# Uni_Seriell.net
KiCad netlist of a schematic drawn in EAGLE
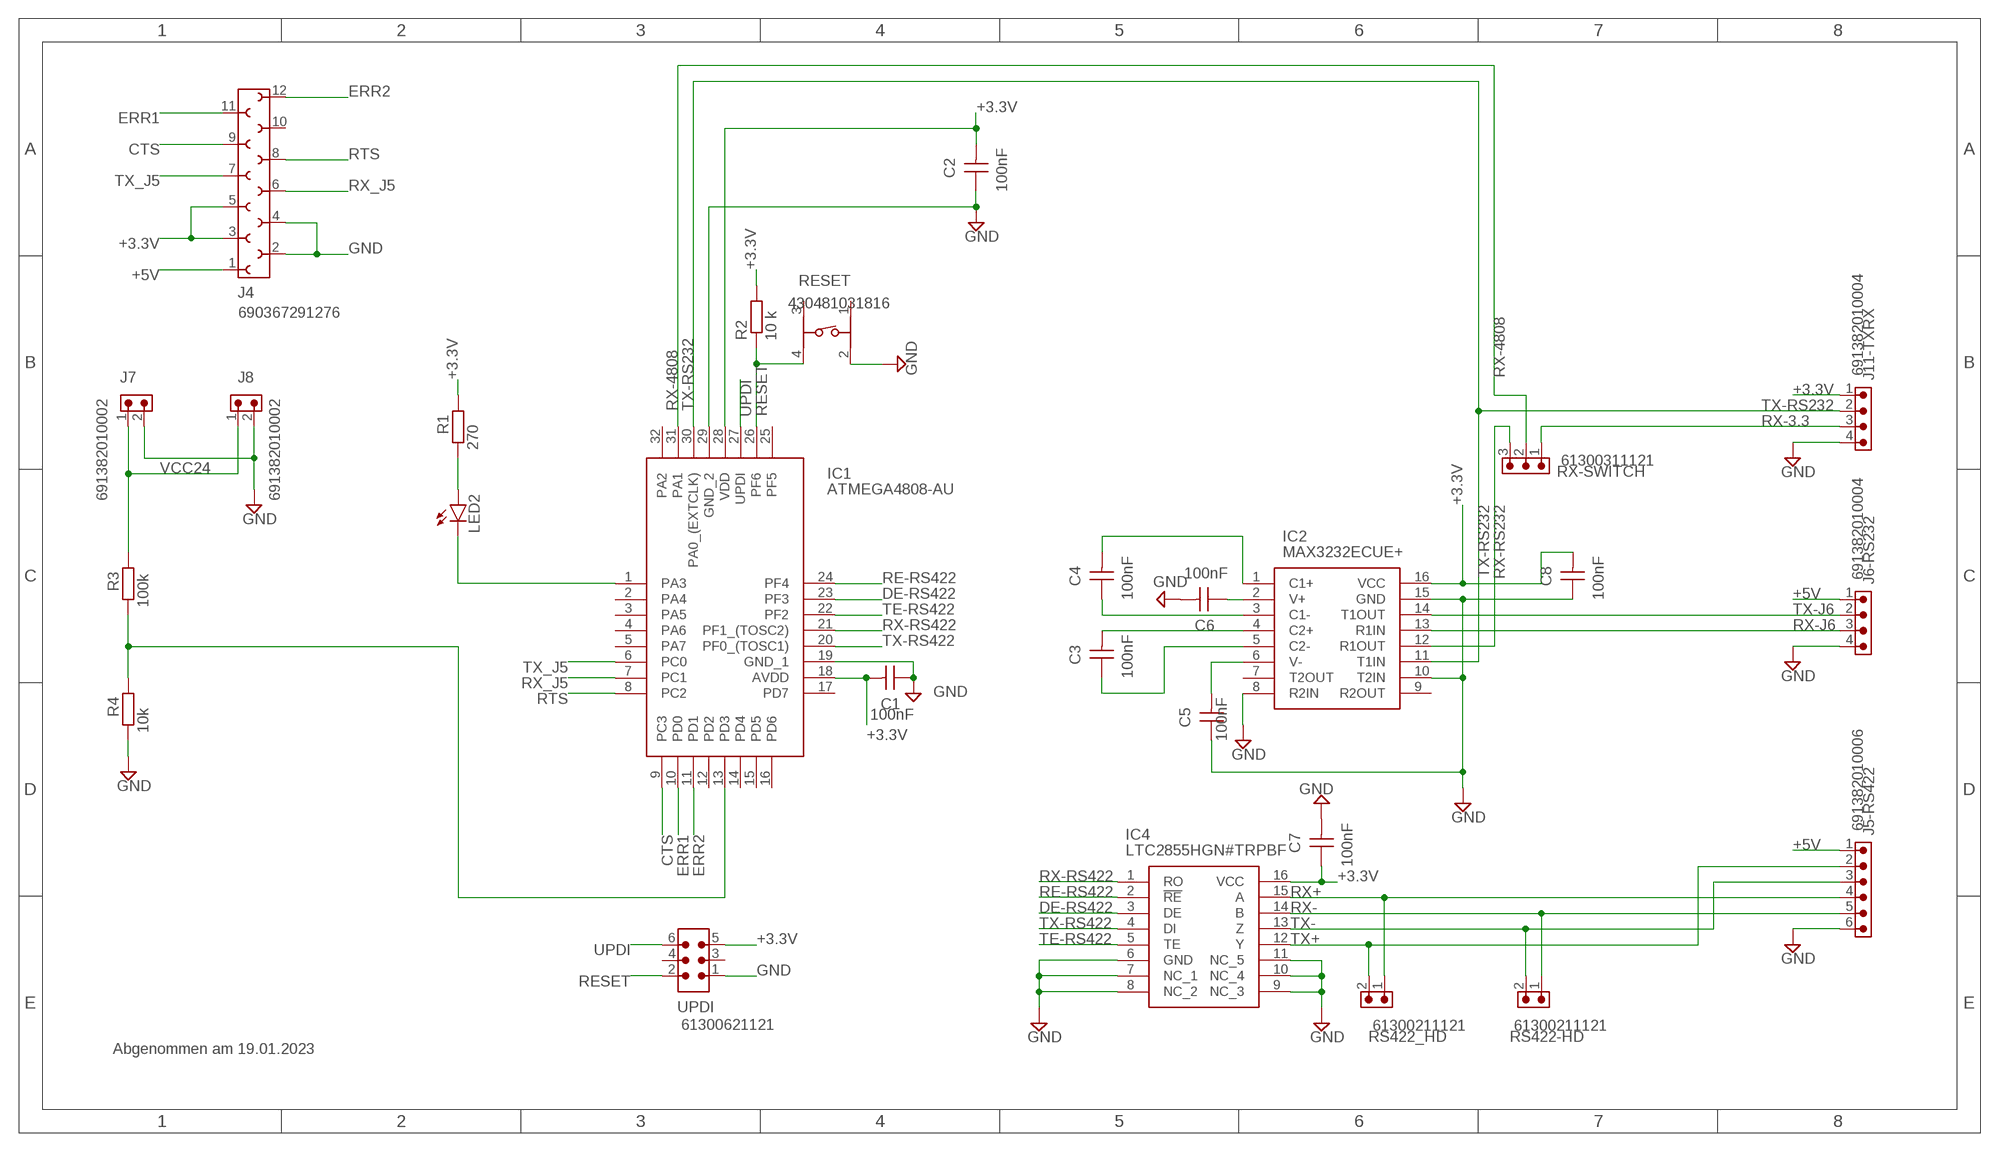
[diagram p0: schematic, sheet 1]

(export (version "E")
  (design (tool "Eeschema 10.0.6"))
  (components
    (comp (ref "C1")
      (value "100nF")
      (footprint "eagle-import:WCAP-CSST_0805")
      (libsource (lib "eagle-import") (part "WCAP-CSST_0805_885382207007"))
    )
    (comp (ref "C2")
      (value "100nF")
      (footprint "eagle-import:WCAP-CSST_0805")
      (libsource (lib "eagle-import") (part "WCAP-CSST_0805_885382207007"))
    )
    (comp (ref "C3")
      (value "100nF")
      (footprint "eagle-import:WCAP-CSST_0805")
      (libsource (lib "eagle-import") (part "WCAP-CSST_0805_885382207007"))
    )
    (comp (ref "C4")
      (value "100nF")
      (footprint "eagle-import:WCAP-CSST_0805")
      (libsource (lib "eagle-import") (part "WCAP-CSST_0805_885382207007"))
    )
    (comp (ref "C5")
      (value "100nF")
      (footprint "eagle-import:WCAP-CSST_0805")
      (libsource (lib "eagle-import") (part "WCAP-CSST_0805_885382207007"))
    )
    (comp (ref "C6")
      (value "100nF")
      (footprint "eagle-import:WCAP-CSST_0805")
      (libsource (lib "eagle-import") (part "WCAP-CSST_0805_885382207007"))
    )
    (comp (ref "C7")
      (value "100nF")
      (footprint "eagle-import:WCAP-CSST_0805")
      (libsource (lib "eagle-import") (part "WCAP-CSST_0805_885382207007"))
    )
    (comp (ref "C8")
      (value "100nF")
      (footprint "eagle-import:WCAP-CSST_0805")
      (libsource (lib "eagle-import") (part "WCAP-CSST_0805_885382207007"))
    )
    (comp (ref "IC1")
      (value "ATMEGA4808-AU")
      (footprint "eagle-import:QFP80P900X900X120-32N")
      (fields (field (name "MOUSER_PART_NUMBER") "556-ATMEGA4808-AU"))
      (libsource (lib "eagle-import") (part "ATMEGA4808-AU"))
    )
    (comp (ref "IC2")
      (value "MAX3232ECUE+")
      (footprint "eagle-import:SOP65P640X110-16N")
      (fields (field (name "MOUSER_PART_NUMBER") "700-MAX3232ECUE"))
      (libsource (lib "eagle-import") (part "MAX3232ECUE+"))
    )
    (comp (ref "IC4")
      (value "LTC2855HGN#TRPBF")
      (footprint "eagle-import:SOP64P601X175-16N")
      (fields (field (name "MOUSER_PART_NUMBER") "584-LTC2855HGN#TRPBF"))
      (libsource (lib "eagle-import") (part "LTC2855HGN#TRPBF"))
    )
    (comp (ref "J4")
      (value "690367291276")
      (footprint "eagle-import:690367291276")
      (libsource (lib "eagle-import") (part "690367291276"))
    )
    (comp (ref "J5-RS422")
      (value "691382010006")
      (footprint "eagle-import:691382010006")
      (libsource (lib "eagle-import") (part "691382010006"))
    )
    (comp (ref "J6-RS232")
      (value "691382010004")
      (footprint "eagle-import:691382010004")
      (libsource (lib "eagle-import") (part "691382010004"))
    )
    (comp (ref "J7")
      (value "691382010002")
      (footprint "eagle-import:691382010002")
      (libsource (lib "eagle-import") (part "691382010002"))
    )
    (comp (ref "J8")
      (value "691382010002")
      (footprint "eagle-import:691382010002")
      (libsource (lib "eagle-import") (part "691382010002"))
    )
    (comp (ref "J11-TXRX")
      (value "691382010004")
      (footprint "eagle-import:691382010004")
      (libsource (lib "eagle-import") (part "691382010004"))
    )
    (comp (ref "LED2")
      (value "LEDCHIP-LED0805")
      (footprint "eagle-import:CHIP-LED0805")
      (libsource (lib "eagle-import") (part "LEDCHIP-LED0805"))
    )
    (comp (ref "R1")
      (value "270")
      (footprint "eagle-import:R0805")
      (libsource (lib "eagle-import") (part "R-EU_R0805"))
    )
    (comp (ref "R2")
      (value "10 k")
      (footprint "eagle-import:R0805")
      (libsource (lib "eagle-import") (part "R-EU_R0805"))
    )
    (comp (ref "R3")
      (value "100k")
      (footprint "eagle-import:R0805")
      (libsource (lib "eagle-import") (part "R-EU_R0805"))
    )
    (comp (ref "R4")
      (value "10k")
      (footprint "eagle-import:R0805")
      (libsource (lib "eagle-import") (part "R-EU_R0805"))
    )
    (comp (ref "RESET")
      (value "430481031816")
      (footprint "eagle-import:430481031816")
      (libsource (lib "eagle-import") (part "430481031816"))
    )
    (comp (ref "RS422-HD")
      (value "61300211121")
      (footprint "eagle-import:61300211121")
      (libsource (lib "eagle-import") (part "6130XX11121_61300211121"))
    )
    (comp (ref "RS422_HD")
      (value "61300211121")
      (footprint "eagle-import:61300211121")
      (libsource (lib "eagle-import") (part "6130XX11121_61300211121"))
    )
    (comp (ref "RX-SWITCH")
      (value "61300311121")
      (footprint "eagle-import:61300311121")
      (libsource (lib "eagle-import") (part "6130XX11121_61300311121"))
    )
    (comp (ref "UPDI")
      (value "61300621121")
      (footprint "eagle-import:61300621121")
      (libsource (lib "eagle-import") (part "6130XX21121_61300621121"))
    )
  )
  (nets
    (net (code "1") (name "/+3.3V") (class "Default")
      (node (ref "C1") (pin "2") (pinfunction "2_2") (pintype "passive"))
      (node (ref "C2") (pin "2") (pinfunction "2_2") (pintype "passive"))
      (node (ref "C7") (pin "1") (pinfunction "1_1") (pintype "passive"))
      (node (ref "C8") (pin "2") (pinfunction "2_2") (pintype "passive"))
      (node (ref "IC1") (pin "18") (pinfunction "AVDD_18") (pintype "bidirectional"))
      (node (ref "IC1") (pin "28") (pinfunction "VDD_28") (pintype "bidirectional"))
      (node (ref "IC2") (pin "16") (pinfunction "VCC_16") (pintype "power_in"))
      (node (ref "IC4") (pin "16") (pinfunction "VCC_16") (pintype "bidirectional"))
      (node (ref "J11-TXRX") (pin "1") (pinfunction "1_1") (pintype "passive"))
      (node (ref "J4") (pin "3") (pinfunction "3_3") (pintype "passive"))
      (node (ref "J4") (pin "5") (pinfunction "5_5") (pintype "passive"))
      (node (ref "R1") (pin "2") (pinfunction "2_2") (pintype "passive"))
      (node (ref "R2") (pin "2") (pinfunction "2_2") (pintype "passive"))
      (node (ref "UPDI") (pin "5") (pinfunction "5_5") (pintype "passive"))
    )
    (net (code "2") (name "/+5V") (class "Default")
      (node (ref "J4") (pin "1") (pinfunction "1_1") (pintype "passive"))
      (node (ref "J5-RS422") (pin "1") (pinfunction "1_1") (pintype "passive"))
      (node (ref "J6-RS232") (pin "1") (pinfunction "1_1") (pintype "passive"))
    )
    (net (code "3") (name "/CTS") (class "Default")
      (node (ref "IC1") (pin "9") (pinfunction "PC3_9") (pintype "bidirectional"))
      (node (ref "J4") (pin "9") (pinfunction "9_9") (pintype "passive"))
    )
    (net (code "4") (name "/DE-RS422") (class "Default")
      (node (ref "IC1") (pin "23") (pinfunction "PF3_23") (pintype "bidirectional"))
      (node (ref "IC4") (pin "3") (pinfunction "DE_3") (pintype "bidirectional"))
    )
    (net (code "5") (name "/ERR1") (class "Default")
      (node (ref "IC1") (pin "10") (pinfunction "PD0_10") (pintype "bidirectional"))
      (node (ref "J4") (pin "11") (pinfunction "11_11") (pintype "passive"))
    )
    (net (code "6") (name "/ERR2") (class "Default")
      (node (ref "IC1") (pin "11") (pinfunction "PD1_11") (pintype "bidirectional"))
      (node (ref "J4") (pin "12") (pinfunction "12_12") (pintype "passive"))
    )
    (net (code "7") (name "/RE-RS422") (class "Default")
      (node (ref "IC1") (pin "24") (pinfunction "PF4_24") (pintype "bidirectional"))
      (node (ref "IC4") (pin "2") (pinfunction "~{RE}_2") (pintype "bidirectional"))
    )
    (net (code "8") (name "/RESET") (class "Default")
      (node (ref "IC1") (pin "26") (pinfunction "PF6_26") (pintype "bidirectional"))
      (node (ref "R2") (pin "1") (pinfunction "1_1") (pintype "passive"))
      (node (ref "RESET") (pin "4") (pinfunction "4_4") (pintype "passive"))
      (node (ref "UPDI") (pin "2") (pinfunction "2_2") (pintype "passive"))
    )
    (net (code "9") (name "/RTS") (class "Default")
      (node (ref "IC1") (pin "8") (pinfunction "PC2_8") (pintype "bidirectional"))
      (node (ref "J4") (pin "8") (pinfunction "8_8") (pintype "passive"))
    )
    (net (code "10") (name "/RX+") (class "Default")
      (node (ref "IC4") (pin "15") (pinfunction "A_15") (pintype "bidirectional"))
      (node (ref "J5-RS422") (pin "4") (pinfunction "4_4") (pintype "passive"))
      (node (ref "RS422_HD") (pin "1") (pinfunction "1_1") (pintype "passive"))
    )
    (net (code "11") (name "/RX-") (class "Default")
      (node (ref "IC4") (pin "14") (pinfunction "B_14") (pintype "bidirectional"))
      (node (ref "J5-RS422") (pin "5") (pinfunction "5_5") (pintype "passive"))
      (node (ref "RS422-HD") (pin "1") (pinfunction "1_1") (pintype "passive"))
    )
    (net (code "12") (name "/RX-3.3") (class "Default")
      (node (ref "J11-TXRX") (pin "3") (pinfunction "3_3") (pintype "passive"))
      (node (ref "RX-SWITCH") (pin "1") (pinfunction "1_1") (pintype "passive"))
    )
    (net (code "13") (name "/RX-4808") (class "Default")
      (node (ref "IC1") (pin "31") (pinfunction "PA1_31") (pintype "bidirectional"))
      (node (ref "RX-SWITCH") (pin "2") (pinfunction "2_2") (pintype "passive"))
    )
    (net (code "14") (name "/RX-J6") (class "Default")
      (node (ref "IC2") (pin "13") (pinfunction "R1IN_13") (pintype "input"))
      (node (ref "J6-RS232") (pin "3") (pinfunction "3_3") (pintype "passive"))
    )
    (net (code "15") (name "/RX-RS232") (class "Default")
      (node (ref "IC2") (pin "12") (pinfunction "R1OUT_12") (pintype "output"))
      (node (ref "RX-SWITCH") (pin "3") (pinfunction "3_3") (pintype "passive"))
    )
    (net (code "16") (name "/RX-RS422") (class "Default")
      (node (ref "IC1") (pin "21") (pinfunction "PF1_(TOSC2)_21") (pintype "bidirectional"))
      (node (ref "IC4") (pin "1") (pinfunction "RO_1") (pintype "bidirectional"))
    )
    (net (code "17") (name "/RX_J5") (class "Default")
      (node (ref "IC1") (pin "7") (pinfunction "PC1_7") (pintype "bidirectional"))
      (node (ref "J4") (pin "6") (pinfunction "6_6") (pintype "passive"))
    )
    (net (code "18") (name "/TE-RS422") (class "Default")
      (node (ref "IC1") (pin "22") (pinfunction "PF2_22") (pintype "bidirectional"))
      (node (ref "IC4") (pin "5") (pinfunction "TE_5") (pintype "bidirectional"))
    )
    (net (code "19") (name "/TX+") (class "Default")
      (node (ref "IC4") (pin "12") (pinfunction "Y_12") (pintype "bidirectional"))
      (node (ref "J5-RS422") (pin "2") (pinfunction "2_2") (pintype "passive"))
      (node (ref "RS422_HD") (pin "2") (pinfunction "2_2") (pintype "passive"))
    )
    (net (code "20") (name "/TX-") (class "Default")
      (node (ref "IC4") (pin "13") (pinfunction "Z_13") (pintype "bidirectional"))
      (node (ref "J5-RS422") (pin "3") (pinfunction "3_3") (pintype "passive"))
      (node (ref "RS422-HD") (pin "2") (pinfunction "2_2") (pintype "passive"))
    )
    (net (code "21") (name "/TX-J6") (class "Default")
      (node (ref "IC2") (pin "14") (pinfunction "T1OUT_14") (pintype "output"))
      (node (ref "J6-RS232") (pin "2") (pinfunction "2_2") (pintype "passive"))
    )
    (net (code "22") (name "/TX-RS232") (class "Default")
      (node (ref "IC1") (pin "30") (pinfunction "PA0_(EXTCLK)_30") (pintype "bidirectional"))
      (node (ref "IC2") (pin "11") (pinfunction "T1IN_11") (pintype "input"))
      (node (ref "J11-TXRX") (pin "2") (pinfunction "2_2") (pintype "passive"))
    )
    (net (code "23") (name "/TX-RS422") (class "Default")
      (node (ref "IC1") (pin "20") (pinfunction "PF0_(TOSC1)_20") (pintype "bidirectional"))
      (node (ref "IC4") (pin "4") (pinfunction "DI_4") (pintype "bidirectional"))
    )
    (net (code "24") (name "/TX_J5") (class "Default")
      (node (ref "IC1") (pin "6") (pinfunction "PC0_6") (pintype "bidirectional"))
      (node (ref "J4") (pin "7") (pinfunction "7_7") (pintype "passive"))
    )
    (net (code "25") (name "/UPDI") (class "Default")
      (node (ref "IC1") (pin "27") (pinfunction "UPDI_27") (pintype "bidirectional"))
      (node (ref "UPDI") (pin "6") (pinfunction "6_6") (pintype "passive"))
    )
    (net (code "26") (name "/VCC24") (class "Default")
      (node (ref "J7") (pin "1") (pinfunction "1_1") (pintype "passive"))
      (node (ref "J8") (pin "1") (pinfunction "1_1") (pintype "passive"))
      (node (ref "R3") (pin "2") (pinfunction "2_2") (pintype "passive"))
    )
    (net (code "27") (name "GND") (class "Default")
      (node (ref "C1") (pin "1") (pinfunction "1_1") (pintype "passive"))
      (node (ref "C2") (pin "1") (pinfunction "1_1") (pintype "passive"))
      (node (ref "C5") (pin "1") (pinfunction "1_1") (pintype "passive"))
      (node (ref "C6") (pin "2") (pinfunction "2_2") (pintype "passive"))
      (node (ref "C7") (pin "2") (pinfunction "2_2") (pintype "passive"))
      (node (ref "C8") (pin "1") (pinfunction "1_1") (pintype "passive"))
      (node (ref "IC1") (pin "19") (pinfunction "GND_1_19") (pintype "bidirectional"))
      (node (ref "IC1") (pin "29") (pinfunction "GND_2_29") (pintype "bidirectional"))
      (node (ref "IC2") (pin "10") (pinfunction "T2IN_10") (pintype "input"))
      (node (ref "IC2") (pin "15") (pinfunction "GND_15") (pintype "power_in"))
      (node (ref "IC2") (pin "8") (pinfunction "R2IN_8") (pintype "input"))
      (node (ref "IC4") (pin "10") (pinfunction "NC_4_10") (pintype "bidirectional"))
      (node (ref "IC4") (pin "11") (pinfunction "NC_5_11") (pintype "bidirectional"))
      (node (ref "IC4") (pin "6") (pinfunction "GND_6") (pintype "bidirectional"))
      (node (ref "IC4") (pin "7") (pinfunction "NC_1_7") (pintype "bidirectional"))
      (node (ref "IC4") (pin "8") (pinfunction "NC_2_8") (pintype "bidirectional"))
      (node (ref "IC4") (pin "9") (pinfunction "NC_3_9") (pintype "bidirectional"))
      (node (ref "J11-TXRX") (pin "4") (pinfunction "4_4") (pintype "passive"))
      (node (ref "J4") (pin "2") (pinfunction "2_2") (pintype "passive"))
      (node (ref "J4") (pin "4") (pinfunction "4_4") (pintype "passive"))
      (node (ref "J5-RS422") (pin "6") (pinfunction "6_6") (pintype "passive"))
      (node (ref "J6-RS232") (pin "4") (pinfunction "4_4") (pintype "passive"))
      (node (ref "J7") (pin "2") (pinfunction "2_2") (pintype "passive"))
      (node (ref "J8") (pin "2") (pinfunction "2_2") (pintype "passive"))
      (node (ref "R4") (pin "1") (pinfunction "1_1") (pintype "passive"))
      (node (ref "RESET") (pin "2") (pinfunction "2_2") (pintype "passive"))
      (node (ref "UPDI") (pin "1") (pinfunction "1_1") (pintype "passive"))
    )
    (net (code "28") (name "Net-(IC1-PA3)") (class "Default")
      (node (ref "IC1") (pin "1") (pinfunction "PA3_1") (pintype "bidirectional"))
      (node (ref "LED2") (pin "C") (pinfunction "C_C") (pintype "passive"))
    )
    (net (code "29") (name "Net-(IC1-PD3)") (class "Default")
      (node (ref "IC1") (pin "13") (pinfunction "PD3_13") (pintype "bidirectional"))
      (node (ref "R3") (pin "1") (pinfunction "1_1") (pintype "passive"))
      (node (ref "R4") (pin "2") (pinfunction "2_2") (pintype "passive"))
    )
    (net (code "30") (name "Net-(IC2-C1+)") (class "Default")
      (node (ref "C4") (pin "2") (pinfunction "2_2") (pintype "passive"))
      (node (ref "IC2") (pin "1") (pinfunction "C1+_1") (pintype "bidirectional"))
    )
    (net (code "31") (name "Net-(IC2-C1-)") (class "Default")
      (node (ref "C4") (pin "1") (pinfunction "1_1") (pintype "passive"))
      (node (ref "IC2") (pin "3") (pinfunction "C1-_3") (pintype "bidirectional"))
    )
    (net (code "32") (name "Net-(IC2-C2+)") (class "Default")
      (node (ref "C3") (pin "2") (pinfunction "2_2") (pintype "passive"))
      (node (ref "IC2") (pin "4") (pinfunction "C2+_4") (pintype "bidirectional"))
    )
    (net (code "33") (name "Net-(IC2-C2-)") (class "Default")
      (node (ref "C3") (pin "1") (pinfunction "1_1") (pintype "passive"))
      (node (ref "IC2") (pin "5") (pinfunction "C2-_5") (pintype "bidirectional"))
    )
    (net (code "34") (name "Net-(IC2-V+)") (class "Default")
      (node (ref "C6") (pin "1") (pinfunction "1_1") (pintype "passive"))
      (node (ref "IC2") (pin "2") (pinfunction "V+_2") (pintype "power_in"))
    )
    (net (code "35") (name "Net-(IC2-V-)") (class "Default")
      (node (ref "C5") (pin "2") (pinfunction "2_2") (pintype "passive"))
      (node (ref "IC2") (pin "6") (pinfunction "V-_6") (pintype "power_in"))
    )
    (net (code "36") (name "Net-(LED2-PadA)") (class "Default")
      (node (ref "LED2") (pin "A") (pinfunction "A_A") (pintype "passive"))
      (node (ref "R1") (pin "1") (pinfunction "1_1") (pintype "passive"))
    )
    (net (code "37") (name "unconnected-(IC1-PA2-Pad32)") (class "Default")
      (node (ref "IC1") (pin "32") (pinfunction "PA2_32") (pintype "bidirectional"))
    )
    (net (code "38") (name "unconnected-(IC1-PA4-Pad2)") (class "Default")
      (node (ref "IC1") (pin "2") (pinfunction "PA4_2") (pintype "bidirectional"))
    )
    (net (code "39") (name "unconnected-(IC1-PA5-Pad3)") (class "Default")
      (node (ref "IC1") (pin "3") (pinfunction "PA5_3") (pintype "bidirectional"))
    )
    (net (code "40") (name "unconnected-(IC1-PA6-Pad4)") (class "Default")
      (node (ref "IC1") (pin "4") (pinfunction "PA6_4") (pintype "bidirectional"))
    )
    (net (code "41") (name "unconnected-(IC1-PA7-Pad5)") (class "Default")
      (node (ref "IC1") (pin "5") (pinfunction "PA7_5") (pintype "bidirectional"))
    )
    (net (code "42") (name "unconnected-(IC1-PD2-Pad12)") (class "Default")
      (node (ref "IC1") (pin "12") (pinfunction "PD2_12") (pintype "bidirectional"))
    )
    (net (code "43") (name "unconnected-(IC1-PD4-Pad14)") (class "Default")
      (node (ref "IC1") (pin "14") (pinfunction "PD4_14") (pintype "bidirectional"))
    )
    (net (code "44") (name "unconnected-(IC1-PD5-Pad15)") (class "Default")
      (node (ref "IC1") (pin "15") (pinfunction "PD5_15") (pintype "bidirectional"))
    )
    (net (code "45") (name "unconnected-(IC1-PD6-Pad16)") (class "Default")
      (node (ref "IC1") (pin "16") (pinfunction "PD6_16") (pintype "bidirectional"))
    )
    (net (code "46") (name "unconnected-(IC1-PD7-Pad17)") (class "Default")
      (node (ref "IC1") (pin "17") (pinfunction "PD7_17") (pintype "bidirectional"))
    )
    (net (code "47") (name "unconnected-(IC1-PF5-Pad25)") (class "Default")
      (node (ref "IC1") (pin "25") (pinfunction "PF5_25") (pintype "bidirectional"))
    )
    (net (code "48") (name "unconnected-(IC2-R2OUT-Pad9)") (class "Default")
      (node (ref "IC2") (pin "9") (pinfunction "R2OUT_9") (pintype "output"))
    )
    (net (code "49") (name "unconnected-(IC2-T2OUT-Pad7)") (class "Default")
      (node (ref "IC2") (pin "7") (pinfunction "T2OUT_7") (pintype "output"))
    )
    (net (code "50") (name "unconnected-(J4-Pad10)") (class "Default")
      (node (ref "J4") (pin "10") (pinfunction "10_10") (pintype "passive"))
    )
    (net (code "51") (name "unconnected-(RESET-Pad1)") (class "Default")
      (node (ref "RESET") (pin "1") (pinfunction "1_1") (pintype "passive"))
    )
    (net (code "52") (name "unconnected-(RESET-Pad3)") (class "Default")
      (node (ref "RESET") (pin "3") (pinfunction "3_3") (pintype "passive"))
    )
    (net (code "53") (name "unconnected-(UPDI-Pad3)") (class "Default")
      (node (ref "UPDI") (pin "3") (pinfunction "3_3") (pintype "passive"))
    )
    (net (code "54") (name "unconnected-(UPDI-Pad4)") (class "Default")
      (node (ref "UPDI") (pin "4") (pinfunction "4_4") (pintype "passive"))
    )
  )
)
